# Digital_Buffer.net
KiCad netlist of a schematic drawn in Altium Designer
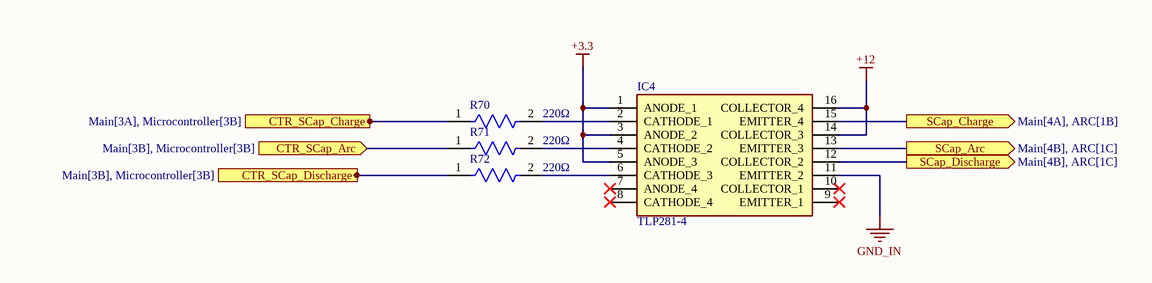
[diagram p0: Digital_Buffer.SchDoc]

(export (version "E")
  (design (tool "Eeschema 10.0.6"))
  (components
    (comp (ref "IC4")
      (value "TLP281-4")
      (footprint "SamacSys:SOIC127P700X210-16N")
      (description "Integrated Circuit")
      (fields (field (name "MOUSER PART NUMBER") "757-TLP281-4"))
      (libsource (lib "*") (part "TLP281-4"))
    )
    (comp (ref "R70")
      (value "220Ω")
      (footprint "FP-RT1206-MFG")
      (description "RES SMD 220 OHM 1% 1/4W 1206")
      (fields
        (field (name "TOLERANCE") "0.0002")
        (field (name "MANUFACTURER PART NUMBER") "RT1206FRE07220RL")
      )
      (libsource (lib "Altium Content Vault") (part "1029c3af85768c4190bb7ad29bc67b5"))
    )
    (comp (ref "R71")
      (value "220Ω")
      (footprint "FP-RT1206-MFG")
      (description "RES SMD 220 OHM 1% 1/4W 1206")
      (fields
        (field (name "TOLERANCE") "0.0002")
        (field (name "MANUFACTURER PART NUMBER") "RT1206FRE07220RL")
      )
      (libsource (lib "Altium Content Vault") (part "1029c3af85768c4190bb7ad29bc67b5"))
    )
    (comp (ref "R72")
      (value "220Ω")
      (footprint "FP-RT1206-MFG")
      (description "RES SMD 220 OHM 1% 1/4W 1206")
      (fields
        (field (name "TOLERANCE") "0.0002")
        (field (name "MANUFACTURER PART NUMBER") "RT1206FRE07220RL")
      )
      (libsource (lib "Altium Content Vault") (part "1029c3af85768c4190bb7ad29bc67b5"))
    )
  )
  (nets
    (net (code "1") (name "+3.3") (class "Default")
      (node (ref "IC4") (pin "1") (pinfunction "ANODE_1_1") (pintype "passive"))
      (node (ref "IC4") (pin "3") (pinfunction "ANODE_2_3") (pintype "passive"))
      (node (ref "IC4") (pin "5") (pinfunction "ANODE_3_5") (pintype "passive"))
    )
    (net (code "2") (name "+12") (class "Default")
      (node (ref "IC4") (pin "14") (pinfunction "COLLECTOR_3_14") (pintype "passive"))
      (node (ref "IC4") (pin "16") (pinfunction "COLLECTOR_4_16") (pintype "passive"))
    )
    (net (code "3") (name "/CTR_SCap_Arc") (class "Default")
      (node (ref "R71") (pin "1") (pinfunction "1_1") (pintype "passive"))
    )
    (net (code "4") (name "/CTR_SCap_Charge") (class "Default")
      (node (ref "R70") (pin "1") (pinfunction "1_1") (pintype "passive"))
    )
    (net (code "5") (name "/CTR_SCap_Discharge") (class "Default")
      (node (ref "R72") (pin "1") (pinfunction "1_1") (pintype "passive"))
    )
    (net (code "6") (name "/SCap_Arc") (class "Default")
      (node (ref "IC4") (pin "13") (pinfunction "EMITTER_3_13") (pintype "passive"))
    )
    (net (code "7") (name "/SCap_Charge") (class "Default")
      (node (ref "IC4") (pin "15") (pinfunction "EMITTER_4_15") (pintype "passive"))
    )
    (net (code "8") (name "/SCap_Discharge") (class "Default")
      (node (ref "IC4") (pin "12") (pinfunction "COLLECTOR_2_12") (pintype "passive"))
    )
    (net (code "9") (name "GND_IN") (class "Default")
      (node (ref "IC4") (pin "11") (pinfunction "EMITTER_2_11") (pintype "passive"))
    )
    (net (code "10") (name "Net-(IC4-CATHODE_1)") (class "Default")
      (node (ref "IC4") (pin "2") (pinfunction "CATHODE_1_2") (pintype "passive"))
      (node (ref "R70") (pin "2") (pinfunction "2_2") (pintype "passive"))
    )
    (net (code "11") (name "Net-(IC4-CATHODE_2)") (class "Default")
      (node (ref "IC4") (pin "4") (pinfunction "CATHODE_2_4") (pintype "passive"))
      (node (ref "R71") (pin "2") (pinfunction "2_2") (pintype "passive"))
    )
    (net (code "12") (name "Net-(IC4-CATHODE_3)") (class "Default")
      (node (ref "IC4") (pin "6") (pinfunction "CATHODE_3_6") (pintype "passive"))
      (node (ref "R72") (pin "2") (pinfunction "2_2") (pintype "passive"))
    )
    (net (code "13") (name "unconnected-(IC4-ANODE_4-Pad7)") (class "Default")
      (node (ref "IC4") (pin "7") (pinfunction "ANODE_4_7") (pintype "passive+no_connect"))
    )
    (net (code "14") (name "unconnected-(IC4-CATHODE_4-Pad8)") (class "Default")
      (node (ref "IC4") (pin "8") (pinfunction "CATHODE_4_8") (pintype "passive+no_connect"))
    )
    (net (code "15") (name "unconnected-(IC4-COLLECTOR_1-Pad10)") (class "Default")
      (node (ref "IC4") (pin "10") (pinfunction "COLLECTOR_1_10") (pintype "passive+no_connect"))
    )
    (net (code "16") (name "unconnected-(IC4-EMITTER_1-Pad9)") (class "Default")
      (node (ref "IC4") (pin "9") (pinfunction "EMITTER_1_9") (pintype "passive+no_connect"))
    )
  )
)
